# Power.net
KiCad netlist of a schematic drawn in Altium Designer
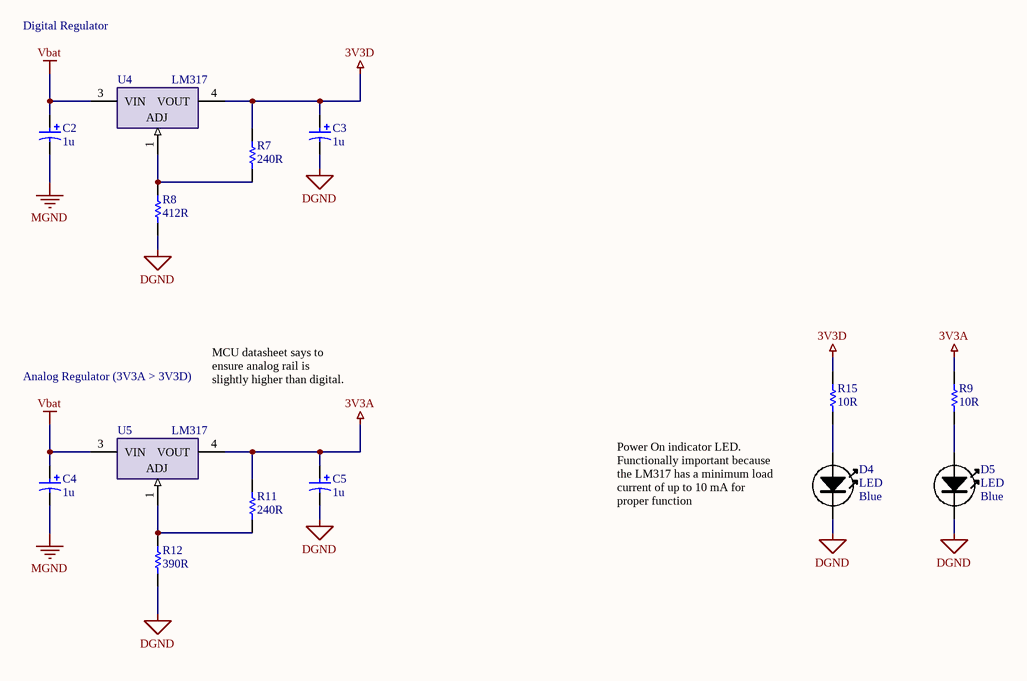
[diagram p0: Power.SchDoc]

(export (version "E")
  (design (tool "Eeschema 10.0.6"))
  (components
    (comp (ref "C2")
      (value "1u")
      (footprint "C1206_tant_low_density")
      (description "Through-hole tantalum capacitor")
      (fields (field (name "Comment") "CapTant"))
      (libsource (lib "passives") (part "CapTant"))
    )
    (comp (ref "C3")
      (value "1u")
      (footprint "C1206_tant_low_density")
      (description "Through-hole tantalum capacitor")
      (fields (field (name "Comment") "CapTant"))
      (libsource (lib "passives") (part "CapTant"))
    )
    (comp (ref "C4")
      (value "1u")
      (footprint "C1206_tant_low_density")
      (description "Through-hole tantalum capacitor")
      (fields (field (name "Comment") "CapTant"))
      (libsource (lib "passives") (part "CapTant"))
    )
    (comp (ref "C5")
      (value "1u")
      (footprint "C1206_tant_low_density")
      (description "Through-hole tantalum capacitor")
      (fields (field (name "Comment") "CapTant"))
      (libsource (lib "passives") (part "CapTant"))
    )
    (comp (ref "D4")
      (value "LED")
      (footprint "LED0805")
      (description "Light-emitting diode")
      (fields (field (name "ALTIUM_VALUE") "Blue"))
      (libsource (lib "passives") (part "LED"))
    )
    (comp (ref "D5")
      (value "LED")
      (footprint "LED0805")
      (description "Light-emitting diode")
      (fields (field (name "ALTIUM_VALUE") "Blue"))
      (libsource (lib "passives") (part "LED"))
    )
    (comp (ref "R7")
      (value "240R")
      (footprint "R0805_med_density")
      (description "SMD Chip resistor")
      (fields (field (name "TOLERANCE") "1%") (field (name "Comment") "ResChip"))
      (libsource (lib "passives") (part "ResChip"))
    )
    (comp (ref "R8")
      (value "412R")
      (footprint "R0805_med_density")
      (description "SMD Chip resistor")
      (fields (field (name "TOLERANCE") "1%") (field (name "Comment") "ResChip"))
      (libsource (lib "passives") (part "ResChip"))
    )
    (comp (ref "R9")
      (value "10R")
      (footprint "R0805_med_density")
      (description "SMD Chip resistor")
      (fields (field (name "Comment") "ResChip"))
      (libsource (lib "passives") (part "ResChip"))
    )
    (comp (ref "R11")
      (value "240R")
      (footprint "R0805_med_density")
      (description "SMD Chip resistor")
      (fields (field (name "TOLERANCE") "1%") (field (name "Comment") "ResChip"))
      (libsource (lib "passives") (part "ResChip"))
    )
    (comp (ref "R12")
      (value "390R")
      (footprint "R0805_med_density")
      (description "SMD Chip resistor")
      (fields (field (name "TOLERANCE") "1%") (field (name "Comment") "ResChip"))
      (libsource (lib "passives") (part "ResChip"))
    )
    (comp (ref "R15")
      (value "10R")
      (footprint "R0805_med_density")
      (description "SMD Chip resistor")
      (fields (field (name "Comment") "ResChip"))
      (libsource (lib "passives") (part "ResChip"))
    )
    (comp (ref "U4")
      (value "LM317")
      (footprint "D-PAK")
      (description "Linear Voltage Regulator")
      (libsource (lib "valves") (part "LM317"))
    )
    (comp (ref "U5")
      (value "LM317")
      (footprint "D-PAK")
      (description "Linear Voltage Regulator")
      (libsource (lib "valves") (part "LM317"))
    )
  )
  (nets
    (net (code "1") (name "3V3A") (class "Default")
      (node (ref "C5") (pin "1") (pinfunction "1_1") (pintype "passive"))
      (node (ref "R11") (pin "2") (pinfunction "2_2") (pintype "passive"))
      (node (ref "R9") (pin "2") (pinfunction "2_2") (pintype "passive"))
      (node (ref "U5") (pin "4") (pinfunction "VOUT_4") (pintype "power_in"))
    )
    (net (code "2") (name "3V3D") (class "Default")
      (node (ref "C3") (pin "1") (pinfunction "1_1") (pintype "passive"))
      (node (ref "R15") (pin "2") (pinfunction "2_2") (pintype "passive"))
      (node (ref "R7") (pin "2") (pinfunction "2_2") (pintype "passive"))
      (node (ref "U4") (pin "4") (pinfunction "VOUT_4") (pintype "power_in"))
    )
    (net (code "3") (name "DGND") (class "Default")
      (node (ref "C3") (pin "2") (pinfunction "2_2") (pintype "passive"))
      (node (ref "C5") (pin "2") (pinfunction "2_2") (pintype "passive"))
      (node (ref "D4") (pin "K") (pintype "passive"))
      (node (ref "D5") (pin "K") (pintype "passive"))
      (node (ref "R12") (pin "1") (pinfunction "1_1") (pintype "passive"))
      (node (ref "R8") (pin "1") (pinfunction "1_1") (pintype "passive"))
    )
    (net (code "4") (name "MGND") (class "Default")
      (node (ref "C2") (pin "2") (pinfunction "2_2") (pintype "passive"))
      (node (ref "C4") (pin "2") (pinfunction "2_2") (pintype "passive"))
    )
    (net (code "5") (name "Net-(D4-PadA)") (class "Default")
      (node (ref "D4") (pin "A") (pintype "passive"))
      (node (ref "R15") (pin "1") (pinfunction "1_1") (pintype "passive"))
    )
    (net (code "6") (name "Net-(D5-PadA)") (class "Default")
      (node (ref "D5") (pin "A") (pintype "passive"))
      (node (ref "R9") (pin "1") (pinfunction "1_1") (pintype "passive"))
    )
    (net (code "7") (name "Net-(U4-ADJ)") (class "Default")
      (node (ref "R7") (pin "1") (pinfunction "1_1") (pintype "passive"))
      (node (ref "R8") (pin "2") (pinfunction "2_2") (pintype "passive"))
      (node (ref "U4") (pin "1") (pinfunction "ADJ_1") (pintype "input"))
    )
    (net (code "8") (name "Net-(U5-ADJ)") (class "Default")
      (node (ref "R11") (pin "1") (pinfunction "1_1") (pintype "passive"))
      (node (ref "R12") (pin "2") (pinfunction "2_2") (pintype "passive"))
      (node (ref "U5") (pin "1") (pinfunction "ADJ_1") (pintype "input"))
    )
    (net (code "9") (name "Vbat") (class "Default")
      (node (ref "C2") (pin "1") (pinfunction "1_1") (pintype "passive"))
      (node (ref "C4") (pin "1") (pinfunction "1_1") (pintype "passive"))
      (node (ref "U4") (pin "3") (pinfunction "VIN_3") (pintype "power_in"))
      (node (ref "U5") (pin "3") (pinfunction "VIN_3") (pintype "power_in"))
    )
  )
)
